# main_module.net
KiCad netlist of a schematic drawn in EAGLE
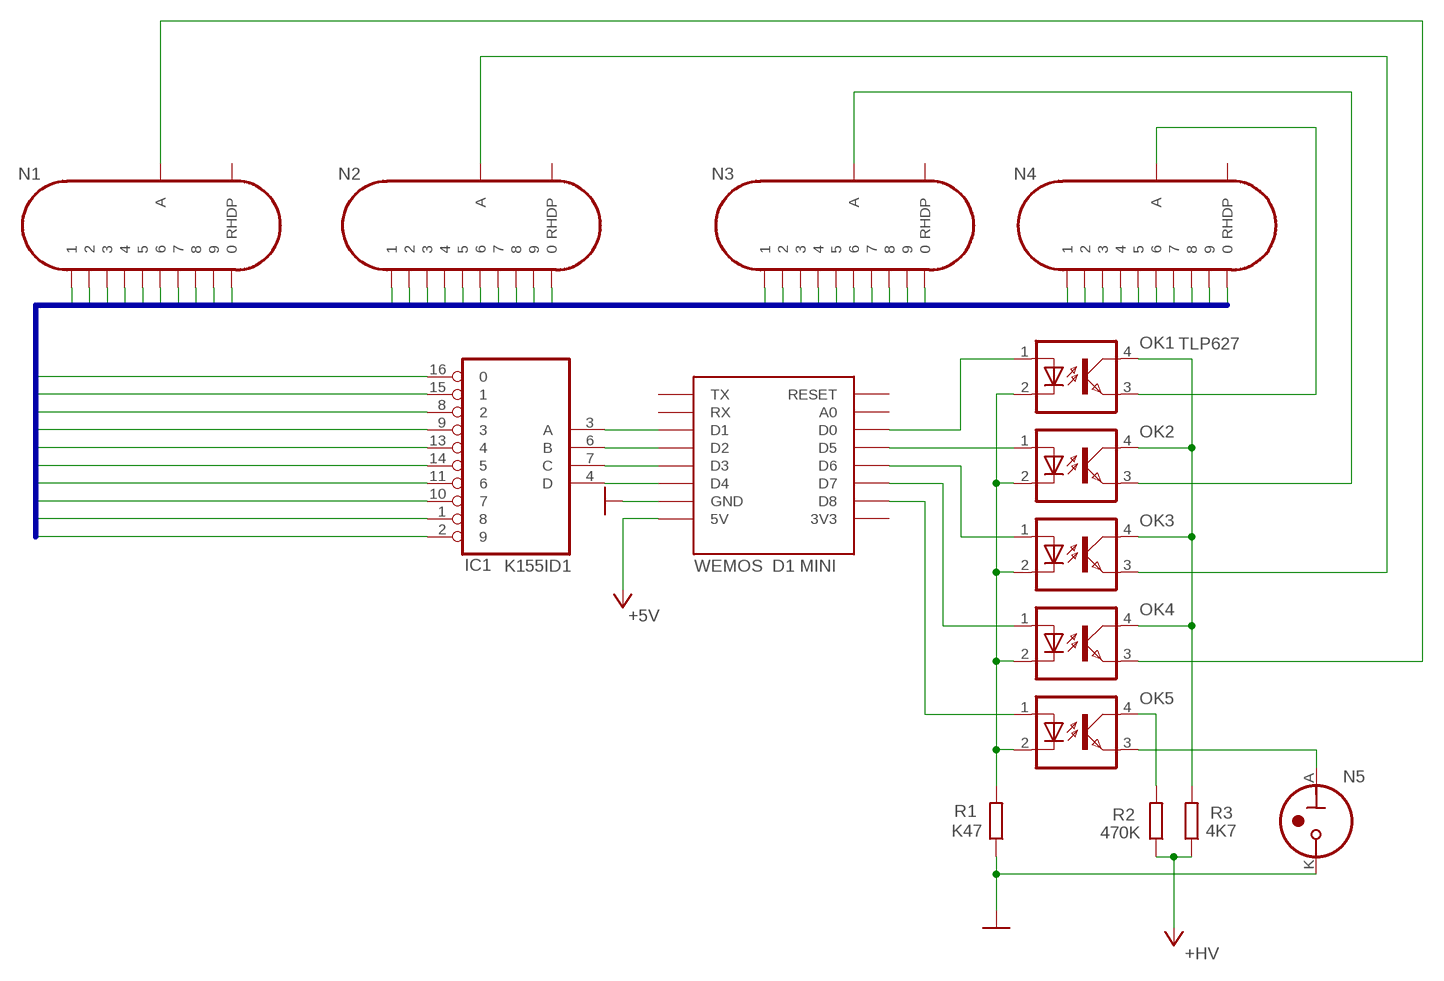
[diagram p0: schematic, sheet 1]

(export (version "E")
  (design (tool "Eeschema 10.0.6"))
  (components
    (comp (ref "IC1")
      (value "K155ID1")
      (footprint "eagle-import:DIL16")
      (libsource (lib "eagle-import") (part "74141N"))
    )
    (comp (ref "N1")
      (value "IN-8-2")
      (footprint "eagle-import:IN-8-2")
      (libsource (lib "eagle-import") (part "IN-8-2"))
    )
    (comp (ref "N2")
      (value "IN-8-2")
      (footprint "eagle-import:IN-8-2")
      (libsource (lib "eagle-import") (part "IN-8-2"))
    )
    (comp (ref "N3")
      (value "IN-8-2")
      (footprint "eagle-import:IN-8-2")
      (libsource (lib "eagle-import") (part "IN-8-2"))
    )
    (comp (ref "N4")
      (value "IN-8-2")
      (footprint "eagle-import:IN-8-2")
      (libsource (lib "eagle-import") (part "IN-8-2"))
    )
    (comp (ref "N5")
      (value "IN-3")
      (footprint "eagle-import:IN-3")
      (libsource (lib "eagle-import") (part "IN-3"))
    )
    (comp (ref "OK1")
      (value "TLP627")
      (footprint "eagle-import:DIL04")
      (libsource (lib "eagle-import") (part "LTV816"))
    )
    (comp (ref "OK2")
      (value "LTV816")
      (footprint "eagle-import:DIL04")
      (libsource (lib "eagle-import") (part "LTV816"))
    )
    (comp (ref "OK3")
      (value "LTV816")
      (footprint "eagle-import:DIL04")
      (libsource (lib "eagle-import") (part "LTV816"))
    )
    (comp (ref "OK4")
      (value "LTV816")
      (footprint "eagle-import:DIL04")
      (libsource (lib "eagle-import") (part "LTV816"))
    )
    (comp (ref "OK5")
      (value "LTV816")
      (footprint "eagle-import:DIL04")
      (libsource (lib "eagle-import") (part "LTV816"))
    )
    (comp (ref "R1")
      (value "K47")
      (footprint "eagle-import:0207_10")
      (libsource (lib "eagle-import") (part "R-EU_0207/10"))
    )
    (comp (ref "R2")
      (value "470K")
      (footprint "eagle-import:0207_10")
      (libsource (lib "eagle-import") (part "R-EU_0207/10"))
    )
    (comp (ref "R3")
      (value "4K7")
      (footprint "eagle-import:0207_10")
      (libsource (lib "eagle-import") (part "R-EU_0207/10"))
    )
    (comp (ref "WEMOS")
      (value "D1 MINI")
      (footprint "eagle-import:WEMOS-D1-MINI")
      (libsource (lib "eagle-import") (part "WEMOS-D1-MINI"))
    )
  )
  (nets
    (net (code "1") (name "+5V") (class "Default")
      (node (ref "WEMOS") (pin "5V") (pinfunction "5V_5V") (pintype "bidirectional"))
    )
    (net (code "2") (name "+HV") (class "Default")
      (node (ref "R2") (pin "1") (pinfunction "1_1") (pintype "passive"))
      (node (ref "R3") (pin "1") (pinfunction "1_1") (pintype "passive"))
    )
    (net (code "3") (name "/N0") (class "Default")
      (node (ref "IC1") (pin "16") (pinfunction "0_16") (pintype "open_collector"))
      (node (ref "N1") (pin "0") (pinfunction "0_0") (pintype "bidirectional"))
      (node (ref "N2") (pin "0") (pinfunction "0_0") (pintype "bidirectional"))
      (node (ref "N3") (pin "0") (pinfunction "0_0") (pintype "bidirectional"))
      (node (ref "N4") (pin "0") (pinfunction "0_0") (pintype "bidirectional"))
    )
    (net (code "4") (name "/N1") (class "Default")
      (node (ref "IC1") (pin "15") (pinfunction "1_15") (pintype "open_collector"))
      (node (ref "N1") (pin "1") (pinfunction "1_1") (pintype "bidirectional"))
      (node (ref "N2") (pin "1") (pinfunction "1_1") (pintype "bidirectional"))
      (node (ref "N3") (pin "1") (pinfunction "1_1") (pintype "bidirectional"))
      (node (ref "N4") (pin "1") (pinfunction "1_1") (pintype "bidirectional"))
    )
    (net (code "5") (name "/N2") (class "Default")
      (node (ref "IC1") (pin "8") (pinfunction "2_8") (pintype "open_collector"))
      (node (ref "N1") (pin "2") (pinfunction "2_2") (pintype "bidirectional"))
      (node (ref "N2") (pin "2") (pinfunction "2_2") (pintype "bidirectional"))
      (node (ref "N3") (pin "2") (pinfunction "2_2") (pintype "bidirectional"))
      (node (ref "N4") (pin "2") (pinfunction "2_2") (pintype "bidirectional"))
    )
    (net (code "6") (name "/N3") (class "Default")
      (node (ref "IC1") (pin "9") (pinfunction "3_9") (pintype "open_collector"))
      (node (ref "N1") (pin "3") (pinfunction "3_3") (pintype "bidirectional"))
      (node (ref "N2") (pin "3") (pinfunction "3_3") (pintype "bidirectional"))
      (node (ref "N3") (pin "3") (pinfunction "3_3") (pintype "bidirectional"))
      (node (ref "N4") (pin "3") (pinfunction "3_3") (pintype "bidirectional"))
    )
    (net (code "7") (name "/N4") (class "Default")
      (node (ref "IC1") (pin "13") (pinfunction "4_13") (pintype "open_collector"))
      (node (ref "N1") (pin "4") (pinfunction "4_4") (pintype "bidirectional"))
      (node (ref "N2") (pin "4") (pinfunction "4_4") (pintype "bidirectional"))
      (node (ref "N3") (pin "4") (pinfunction "4_4") (pintype "bidirectional"))
      (node (ref "N4") (pin "4") (pinfunction "4_4") (pintype "bidirectional"))
    )
    (net (code "8") (name "/N5") (class "Default")
      (node (ref "IC1") (pin "14") (pinfunction "5_14") (pintype "open_collector"))
      (node (ref "N1") (pin "5") (pinfunction "5_5") (pintype "bidirectional"))
      (node (ref "N2") (pin "5") (pinfunction "5_5") (pintype "bidirectional"))
      (node (ref "N3") (pin "5") (pinfunction "5_5") (pintype "bidirectional"))
      (node (ref "N4") (pin "5") (pinfunction "5_5") (pintype "bidirectional"))
    )
    (net (code "9") (name "/N6") (class "Default")
      (node (ref "IC1") (pin "11") (pinfunction "6_11") (pintype "open_collector"))
      (node (ref "N1") (pin "6") (pinfunction "6_6") (pintype "bidirectional"))
      (node (ref "N2") (pin "6") (pinfunction "6_6") (pintype "bidirectional"))
      (node (ref "N3") (pin "6") (pinfunction "6_6") (pintype "bidirectional"))
      (node (ref "N4") (pin "6") (pinfunction "6_6") (pintype "bidirectional"))
    )
    (net (code "10") (name "/N7") (class "Default")
      (node (ref "IC1") (pin "10") (pinfunction "7_10") (pintype "open_collector"))
      (node (ref "N1") (pin "7") (pinfunction "7_7") (pintype "bidirectional"))
      (node (ref "N2") (pin "7") (pinfunction "7_7") (pintype "bidirectional"))
      (node (ref "N3") (pin "7") (pinfunction "7_7") (pintype "bidirectional"))
      (node (ref "N4") (pin "7") (pinfunction "7_7") (pintype "bidirectional"))
    )
    (net (code "11") (name "/N8") (class "Default")
      (node (ref "IC1") (pin "1") (pinfunction "8_1") (pintype "open_collector"))
      (node (ref "N1") (pin "8") (pinfunction "8_8") (pintype "bidirectional"))
      (node (ref "N1") (pin "9") (pinfunction "9_9") (pintype "bidirectional"))
      (node (ref "N2") (pin "8") (pinfunction "8_8") (pintype "bidirectional"))
      (node (ref "N3") (pin "8") (pinfunction "8_8") (pintype "bidirectional"))
      (node (ref "N4") (pin "8") (pinfunction "8_8") (pintype "bidirectional"))
    )
    (net (code "12") (name "/N9") (class "Default")
      (node (ref "IC1") (pin "2") (pinfunction "9_2") (pintype "open_collector"))
      (node (ref "N2") (pin "9") (pinfunction "9_9") (pintype "bidirectional"))
      (node (ref "N3") (pin "9") (pinfunction "9_9") (pintype "bidirectional"))
      (node (ref "N4") (pin "9") (pinfunction "9_9") (pintype "bidirectional"))
    )
    (net (code "13") (name "GND") (class "Default")
      (node (ref "N5") (pin "K") (pinfunction "K_K") (pintype "bidirectional"))
      (node (ref "R1") (pin "1") (pinfunction "1_1") (pintype "passive"))
      (node (ref "WEMOS") (pin "GND") (pinfunction "GND_GND") (pintype "bidirectional"))
    )
    (net (code "14") (name "Net-(IC1A-A)") (class "Default")
      (node (ref "IC1") (pin "3") (pinfunction "A_3") (pintype "input"))
      (node (ref "WEMOS") (pin "D1") (pinfunction "D1_D1") (pintype "bidirectional"))
    )
    (net (code "15") (name "Net-(IC1A-B)") (class "Default")
      (node (ref "IC1") (pin "6") (pinfunction "B_6") (pintype "input"))
      (node (ref "WEMOS") (pin "D2") (pinfunction "D2_D2") (pintype "bidirectional"))
    )
    (net (code "16") (name "Net-(IC1A-C)") (class "Default")
      (node (ref "IC1") (pin "7") (pinfunction "C_7") (pintype "input"))
      (node (ref "WEMOS") (pin "D3") (pinfunction "D3_D3") (pintype "bidirectional"))
    )
    (net (code "17") (name "Net-(IC1A-D)") (class "Default")
      (node (ref "IC1") (pin "4") (pinfunction "D_4") (pintype "input"))
      (node (ref "WEMOS") (pin "D4") (pinfunction "D4_D4") (pintype "bidirectional"))
    )
    (net (code "18") (name "Net-(OK1-A)") (class "Default")
      (node (ref "OK1") (pin "1") (pinfunction "A_1") (pintype "passive"))
      (node (ref "WEMOS") (pin "D0") (pinfunction "D0_D0") (pintype "bidirectional"))
    )
    (net (code "19") (name "Net-(OK1-C)") (class "Default")
      (node (ref "OK1") (pin "2") (pinfunction "C_2") (pintype "passive"))
      (node (ref "OK2") (pin "2") (pinfunction "C_2") (pintype "passive"))
      (node (ref "OK3") (pin "2") (pinfunction "C_2") (pintype "passive"))
      (node (ref "OK4") (pin "2") (pinfunction "C_2") (pintype "passive"))
      (node (ref "OK5") (pin "2") (pinfunction "C_2") (pintype "passive"))
      (node (ref "R1") (pin "2") (pinfunction "2_2") (pintype "passive"))
    )
    (net (code "20") (name "Net-(OK1-COL)") (class "Default")
      (node (ref "OK1") (pin "4") (pinfunction "COL_4") (pintype "passive"))
      (node (ref "OK2") (pin "4") (pinfunction "COL_4") (pintype "passive"))
      (node (ref "OK3") (pin "4") (pinfunction "COL_4") (pintype "passive"))
      (node (ref "OK4") (pin "4") (pinfunction "COL_4") (pintype "passive"))
      (node (ref "R3") (pin "2") (pinfunction "2_2") (pintype "passive"))
    )
    (net (code "21") (name "Net-(OK1-EMIT)") (class "Default")
      (node (ref "N4") (pin "A") (pinfunction "A_A") (pintype "bidirectional"))
      (node (ref "OK1") (pin "3") (pinfunction "EMIT_3") (pintype "passive"))
    )
    (net (code "22") (name "Net-(OK2-A)") (class "Default")
      (node (ref "OK2") (pin "1") (pinfunction "A_1") (pintype "passive"))
      (node (ref "WEMOS") (pin "D5") (pinfunction "D5_D5") (pintype "bidirectional"))
    )
    (net (code "23") (name "Net-(OK2-EMIT)") (class "Default")
      (node (ref "N3") (pin "A") (pinfunction "A_A") (pintype "bidirectional"))
      (node (ref "OK2") (pin "3") (pinfunction "EMIT_3") (pintype "passive"))
    )
    (net (code "24") (name "Net-(OK3-A)") (class "Default")
      (node (ref "OK3") (pin "1") (pinfunction "A_1") (pintype "passive"))
      (node (ref "WEMOS") (pin "D6") (pinfunction "D6_D6") (pintype "bidirectional"))
    )
    (net (code "25") (name "Net-(OK3-EMIT)") (class "Default")
      (node (ref "N2") (pin "A") (pinfunction "A_A") (pintype "bidirectional"))
      (node (ref "OK3") (pin "3") (pinfunction "EMIT_3") (pintype "passive"))
    )
    (net (code "26") (name "Net-(OK4-A)") (class "Default")
      (node (ref "OK4") (pin "1") (pinfunction "A_1") (pintype "passive"))
      (node (ref "WEMOS") (pin "D7") (pinfunction "D7_D7") (pintype "bidirectional"))
    )
    (net (code "27") (name "Net-(OK4-EMIT)") (class "Default")
      (node (ref "N1") (pin "A") (pinfunction "A_A") (pintype "bidirectional"))
      (node (ref "OK4") (pin "3") (pinfunction "EMIT_3") (pintype "passive"))
    )
    (net (code "28") (name "Net-(OK5-A)") (class "Default")
      (node (ref "OK5") (pin "1") (pinfunction "A_1") (pintype "passive"))
      (node (ref "WEMOS") (pin "D8") (pinfunction "D8_D8") (pintype "bidirectional"))
    )
    (net (code "29") (name "Net-(OK5-COL)") (class "Default")
      (node (ref "OK5") (pin "4") (pinfunction "COL_4") (pintype "passive"))
      (node (ref "R2") (pin "2") (pinfunction "2_2") (pintype "passive"))
    )
    (net (code "30") (name "Net-(OK5-EMIT)") (class "Default")
      (node (ref "N5") (pin "A") (pinfunction "A_A") (pintype "bidirectional"))
      (node (ref "OK5") (pin "3") (pinfunction "EMIT_3") (pintype "passive"))
    )
    (net (code "31") (name "unconnected-(N1-RHDP-Pad.)") (class "Default")
      (node (ref "N1") (pin ".") (pinfunction "RHDP_.") (pintype "bidirectional"))
    )
    (net (code "32") (name "unconnected-(N2-RHDP-Pad.)") (class "Default")
      (node (ref "N2") (pin ".") (pinfunction "RHDP_.") (pintype "bidirectional"))
    )
    (net (code "33") (name "unconnected-(N3-RHDP-Pad.)") (class "Default")
      (node (ref "N3") (pin ".") (pinfunction "RHDP_.") (pintype "bidirectional"))
    )
    (net (code "34") (name "unconnected-(N4-RHDP-Pad.)") (class "Default")
      (node (ref "N4") (pin ".") (pinfunction "RHDP_.") (pintype "bidirectional"))
    )
    (net (code "35") (name "unconnected-(WEMOS-Pad3V3)") (class "Default")
      (node (ref "WEMOS") (pin "3V3") (pinfunction "3V3_3V3") (pintype "bidirectional"))
    )
    (net (code "36") (name "unconnected-(WEMOS-PadA0)") (class "Default")
      (node (ref "WEMOS") (pin "A0") (pinfunction "A0_A0") (pintype "bidirectional"))
    )
    (net (code "37") (name "unconnected-(WEMOS-PadRESET)") (class "Default")
      (node (ref "WEMOS") (pin "RESET") (pinfunction "RESET_RESET") (pintype "bidirectional"))
    )
    (net (code "38") (name "unconnected-(WEMOS-PadRX)") (class "Default")
      (node (ref "WEMOS") (pin "RX") (pinfunction "RX_RX") (pintype "bidirectional"))
    )
    (net (code "39") (name "unconnected-(WEMOS-PadTX)") (class "Default")
      (node (ref "WEMOS") (pin "TX") (pinfunction "TX_TX") (pintype "bidirectional"))
    )
  )
)
